# CONN.net
KiCad netlist of a schematic drawn in Altium Designer
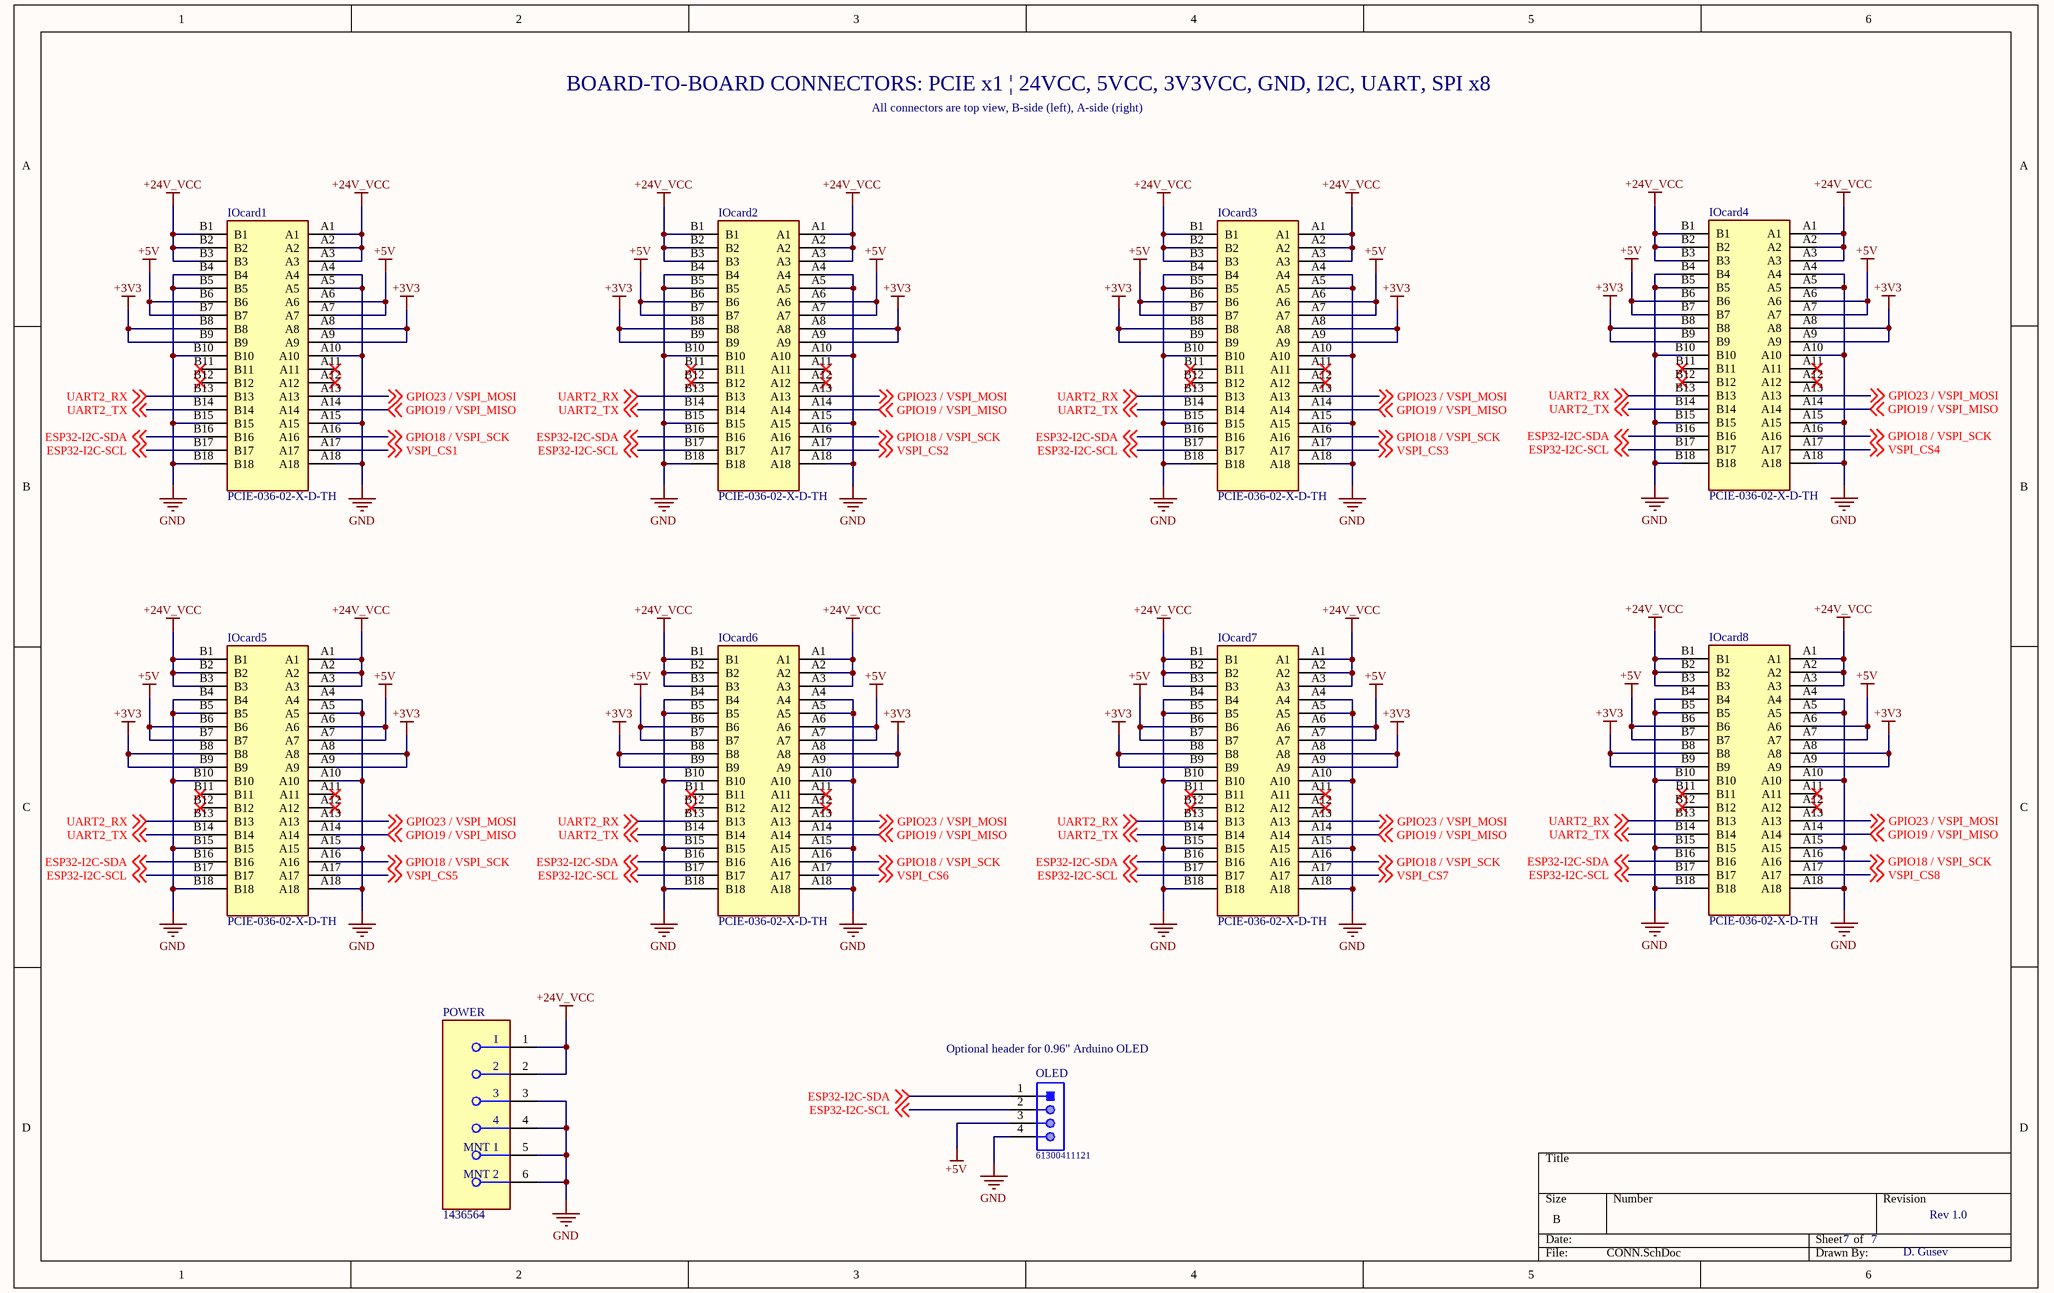
[diagram p0: CONN.SchDoc]

(export (version "E")
  (design (tool "Eeschema 10.0.6"))
  (components
    (comp (ref "IOcard1")
      (value "PCIE-036-02-X-D-TH")
      (footprint "SAMTEC_PCIE-036-02-X-D-TH")
      (description "1.00 mm PCI ExpressÂ® Edge Card Connector")
      (fields (field (name "MF") "Samtec"))
      (libsource (lib "ESP32_INDUSTRIAL_IO_BASEBOARD") (part "PCIE-036-02-X-D-TH"))
    )
    (comp (ref "IOcard2")
      (value "PCIE-036-02-X-D-TH")
      (footprint "SAMTEC_PCIE-036-02-X-D-TH")
      (description "1.00 mm PCI ExpressÂ® Edge Card Connector")
      (fields (field (name "MF") "Samtec"))
      (libsource (lib "ESP32_INDUSTRIAL_IO_BASEBOARD") (part "PCIE-036-02-X-D-TH"))
    )
    (comp (ref "IOcard3")
      (value "PCIE-036-02-X-D-TH")
      (footprint "SAMTEC_PCIE-036-02-X-D-TH")
      (description "1.00 mm PCI ExpressÂ® Edge Card Connector")
      (fields (field (name "MF") "Samtec"))
      (libsource (lib "ESP32_INDUSTRIAL_IO_BASEBOARD") (part "PCIE-036-02-X-D-TH"))
    )
    (comp (ref "IOcard4")
      (value "PCIE-036-02-X-D-TH")
      (footprint "SAMTEC_PCIE-036-02-X-D-TH")
      (description "1.00 mm PCI ExpressÂ® Edge Card Connector")
      (fields (field (name "MF") "Samtec"))
      (libsource (lib "ESP32_INDUSTRIAL_IO_BASEBOARD") (part "PCIE-036-02-X-D-TH"))
    )
    (comp (ref "IOcard5")
      (value "PCIE-036-02-X-D-TH")
      (footprint "SAMTEC_PCIE-036-02-X-D-TH")
      (description "1.00 mm PCI ExpressÂ® Edge Card Connector")
      (fields (field (name "MF") "Samtec"))
      (libsource (lib "ESP32_INDUSTRIAL_IO_BASEBOARD") (part "PCIE-036-02-X-D-TH"))
    )
    (comp (ref "IOcard6")
      (value "PCIE-036-02-X-D-TH")
      (footprint "SAMTEC_PCIE-036-02-X-D-TH")
      (description "1.00 mm PCI ExpressÂ® Edge Card Connector")
      (fields (field (name "MF") "Samtec"))
      (libsource (lib "ESP32_INDUSTRIAL_IO_BASEBOARD") (part "PCIE-036-02-X-D-TH"))
    )
    (comp (ref "IOcard7")
      (value "PCIE-036-02-X-D-TH")
      (footprint "SAMTEC_PCIE-036-02-X-D-TH")
      (description "1.00 mm PCI ExpressÂ® Edge Card Connector")
      (fields (field (name "MF") "Samtec"))
      (libsource (lib "ESP32_INDUSTRIAL_IO_BASEBOARD") (part "PCIE-036-02-X-D-TH"))
    )
    (comp (ref "IOcard8")
      (value "PCIE-036-02-X-D-TH")
      (footprint "SAMTEC_PCIE-036-02-X-D-TH")
      (description "1.00 mm PCI ExpressÂ® Edge Card Connector")
      (fields (field (name "MF") "Samtec"))
      (libsource (lib "ESP32_INDUSTRIAL_IO_BASEBOARD") (part "PCIE-036-02-X-D-TH"))
    )
    (comp (ref "OLED")
      (value "61300411121")
      (footprint "61300411121")
      (description "THT Vertical Pin Header WR-PHD, Pitch 2.54 mm, Single Row, 4 pins")
      (fields (field (name "MANUFACTURER") "Wurth Elektronik") (field (name "PUBLISHER") "WurthElektronik"))
      (libsource (lib "Altium Content Vault") (part "WE-CN-1P-M-R4"))
    )
    (comp (ref "POWER")
      (value "1436564")
      (footprint "FP-1436564-MFG")
      (description "CONN RCPT FMALE 4POS GOLD SOLDER")
      (fields
        (field (name "OCTOPART") "https://octopart.com/1436564-phoenix+contact-12805506")
        (field (name "MANUFACTURER") "Phoenix Contact")
      )
      (libsource (lib "Altium Content Vault") (part "3cf8230c7ca2247c71501eddf00a6f6"))
    )
  )
  (nets
    (net (code "1") (name "+3V3") (class "Default")
      (node (ref "IOcard1") (pin "A8") (pinfunction "A8_A8") (pintype "passive"))
      (node (ref "IOcard1") (pin "A9") (pinfunction "A9_A9") (pintype "passive"))
      (node (ref "IOcard1") (pin "B8") (pinfunction "B8_B8") (pintype "passive"))
      (node (ref "IOcard1") (pin "B9") (pinfunction "B9_B9") (pintype "passive"))
      (node (ref "IOcard2") (pin "A8") (pinfunction "A8_A8") (pintype "passive"))
      (node (ref "IOcard2") (pin "A9") (pinfunction "A9_A9") (pintype "passive"))
      (node (ref "IOcard2") (pin "B8") (pinfunction "B8_B8") (pintype "passive"))
      (node (ref "IOcard2") (pin "B9") (pinfunction "B9_B9") (pintype "passive"))
      (node (ref "IOcard3") (pin "A8") (pinfunction "A8_A8") (pintype "passive"))
      (node (ref "IOcard3") (pin "A9") (pinfunction "A9_A9") (pintype "passive"))
      (node (ref "IOcard3") (pin "B8") (pinfunction "B8_B8") (pintype "passive"))
      (node (ref "IOcard3") (pin "B9") (pinfunction "B9_B9") (pintype "passive"))
      (node (ref "IOcard4") (pin "A8") (pinfunction "A8_A8") (pintype "passive"))
      (node (ref "IOcard4") (pin "A9") (pinfunction "A9_A9") (pintype "passive"))
      (node (ref "IOcard4") (pin "B8") (pinfunction "B8_B8") (pintype "passive"))
      (node (ref "IOcard4") (pin "B9") (pinfunction "B9_B9") (pintype "passive"))
      (node (ref "IOcard5") (pin "A8") (pinfunction "A8_A8") (pintype "passive"))
      (node (ref "IOcard5") (pin "A9") (pinfunction "A9_A9") (pintype "passive"))
      (node (ref "IOcard5") (pin "B8") (pinfunction "B8_B8") (pintype "passive"))
      (node (ref "IOcard5") (pin "B9") (pinfunction "B9_B9") (pintype "passive"))
      (node (ref "IOcard6") (pin "A8") (pinfunction "A8_A8") (pintype "passive"))
      (node (ref "IOcard6") (pin "A9") (pinfunction "A9_A9") (pintype "passive"))
      (node (ref "IOcard6") (pin "B8") (pinfunction "B8_B8") (pintype "passive"))
      (node (ref "IOcard6") (pin "B9") (pinfunction "B9_B9") (pintype "passive"))
      (node (ref "IOcard7") (pin "A8") (pinfunction "A8_A8") (pintype "passive"))
      (node (ref "IOcard7") (pin "A9") (pinfunction "A9_A9") (pintype "passive"))
      (node (ref "IOcard7") (pin "B8") (pinfunction "B8_B8") (pintype "passive"))
      (node (ref "IOcard7") (pin "B9") (pinfunction "B9_B9") (pintype "passive"))
      (node (ref "IOcard8") (pin "A8") (pinfunction "A8_A8") (pintype "passive"))
      (node (ref "IOcard8") (pin "A9") (pinfunction "A9_A9") (pintype "passive"))
      (node (ref "IOcard8") (pin "B8") (pinfunction "B8_B8") (pintype "passive"))
      (node (ref "IOcard8") (pin "B9") (pinfunction "B9_B9") (pintype "passive"))
    )
    (net (code "2") (name "+5V") (class "Default")
      (node (ref "IOcard1") (pin "A6") (pinfunction "A6_A6") (pintype "passive"))
      (node (ref "IOcard1") (pin "A7") (pinfunction "A7_A7") (pintype "passive"))
      (node (ref "IOcard1") (pin "B6") (pinfunction "B6_B6") (pintype "passive"))
      (node (ref "IOcard1") (pin "B7") (pinfunction "B7_B7") (pintype "passive"))
      (node (ref "IOcard2") (pin "A6") (pinfunction "A6_A6") (pintype "passive"))
      (node (ref "IOcard2") (pin "A7") (pinfunction "A7_A7") (pintype "passive"))
      (node (ref "IOcard2") (pin "B6") (pinfunction "B6_B6") (pintype "passive"))
      (node (ref "IOcard2") (pin "B7") (pinfunction "B7_B7") (pintype "passive"))
      (node (ref "IOcard3") (pin "A6") (pinfunction "A6_A6") (pintype "passive"))
      (node (ref "IOcard3") (pin "A7") (pinfunction "A7_A7") (pintype "passive"))
      (node (ref "IOcard3") (pin "B6") (pinfunction "B6_B6") (pintype "passive"))
      (node (ref "IOcard3") (pin "B7") (pinfunction "B7_B7") (pintype "passive"))
      (node (ref "IOcard4") (pin "A6") (pinfunction "A6_A6") (pintype "passive"))
      (node (ref "IOcard4") (pin "A7") (pinfunction "A7_A7") (pintype "passive"))
      (node (ref "IOcard4") (pin "B6") (pinfunction "B6_B6") (pintype "passive"))
      (node (ref "IOcard4") (pin "B7") (pinfunction "B7_B7") (pintype "passive"))
      (node (ref "IOcard5") (pin "A6") (pinfunction "A6_A6") (pintype "passive"))
      (node (ref "IOcard5") (pin "A7") (pinfunction "A7_A7") (pintype "passive"))
      (node (ref "IOcard5") (pin "B6") (pinfunction "B6_B6") (pintype "passive"))
      (node (ref "IOcard5") (pin "B7") (pinfunction "B7_B7") (pintype "passive"))
      (node (ref "IOcard6") (pin "A6") (pinfunction "A6_A6") (pintype "passive"))
      (node (ref "IOcard6") (pin "A7") (pinfunction "A7_A7") (pintype "passive"))
      (node (ref "IOcard6") (pin "B6") (pinfunction "B6_B6") (pintype "passive"))
      (node (ref "IOcard6") (pin "B7") (pinfunction "B7_B7") (pintype "passive"))
      (node (ref "IOcard7") (pin "A6") (pinfunction "A6_A6") (pintype "passive"))
      (node (ref "IOcard7") (pin "A7") (pinfunction "A7_A7") (pintype "passive"))
      (node (ref "IOcard7") (pin "B6") (pinfunction "B6_B6") (pintype "passive"))
      (node (ref "IOcard7") (pin "B7") (pinfunction "B7_B7") (pintype "passive"))
      (node (ref "IOcard8") (pin "A6") (pinfunction "A6_A6") (pintype "passive"))
      (node (ref "IOcard8") (pin "A7") (pinfunction "A7_A7") (pintype "passive"))
      (node (ref "IOcard8") (pin "B6") (pinfunction "B6_B6") (pintype "passive"))
      (node (ref "IOcard8") (pin "B7") (pinfunction "B7_B7") (pintype "passive"))
      (node (ref "OLED") (pin "3") (pinfunction "3_3") (pintype "passive"))
    )
    (net (code "3") (name "+24V_VCC") (class "Default")
      (node (ref "IOcard1") (pin "A1") (pinfunction "A1_A1") (pintype "passive"))
      (node (ref "IOcard1") (pin "A2") (pinfunction "A2_A2") (pintype "passive"))
      (node (ref "IOcard1") (pin "A3") (pinfunction "A3_A3") (pintype "passive"))
      (node (ref "IOcard1") (pin "B1") (pinfunction "B1_B1") (pintype "passive"))
      (node (ref "IOcard1") (pin "B2") (pinfunction "B2_B2") (pintype "passive"))
      (node (ref "IOcard1") (pin "B3") (pinfunction "B3_B3") (pintype "passive"))
      (node (ref "IOcard2") (pin "A1") (pinfunction "A1_A1") (pintype "passive"))
      (node (ref "IOcard2") (pin "A2") (pinfunction "A2_A2") (pintype "passive"))
      (node (ref "IOcard2") (pin "A3") (pinfunction "A3_A3") (pintype "passive"))
      (node (ref "IOcard2") (pin "B1") (pinfunction "B1_B1") (pintype "passive"))
      (node (ref "IOcard2") (pin "B2") (pinfunction "B2_B2") (pintype "passive"))
      (node (ref "IOcard2") (pin "B3") (pinfunction "B3_B3") (pintype "passive"))
      (node (ref "IOcard3") (pin "A1") (pinfunction "A1_A1") (pintype "passive"))
      (node (ref "IOcard3") (pin "A2") (pinfunction "A2_A2") (pintype "passive"))
      (node (ref "IOcard3") (pin "A3") (pinfunction "A3_A3") (pintype "passive"))
      (node (ref "IOcard3") (pin "B1") (pinfunction "B1_B1") (pintype "passive"))
      (node (ref "IOcard3") (pin "B2") (pinfunction "B2_B2") (pintype "passive"))
      (node (ref "IOcard3") (pin "B3") (pinfunction "B3_B3") (pintype "passive"))
      (node (ref "IOcard4") (pin "A1") (pinfunction "A1_A1") (pintype "passive"))
      (node (ref "IOcard4") (pin "A2") (pinfunction "A2_A2") (pintype "passive"))
      (node (ref "IOcard4") (pin "A3") (pinfunction "A3_A3") (pintype "passive"))
      (node (ref "IOcard4") (pin "B1") (pinfunction "B1_B1") (pintype "passive"))
      (node (ref "IOcard4") (pin "B2") (pinfunction "B2_B2") (pintype "passive"))
      (node (ref "IOcard4") (pin "B3") (pinfunction "B3_B3") (pintype "passive"))
      (node (ref "IOcard5") (pin "A1") (pinfunction "A1_A1") (pintype "passive"))
      (node (ref "IOcard5") (pin "A2") (pinfunction "A2_A2") (pintype "passive"))
      (node (ref "IOcard5") (pin "A3") (pinfunction "A3_A3") (pintype "passive"))
      (node (ref "IOcard5") (pin "B1") (pinfunction "B1_B1") (pintype "passive"))
      (node (ref "IOcard5") (pin "B2") (pinfunction "B2_B2") (pintype "passive"))
      (node (ref "IOcard5") (pin "B3") (pinfunction "B3_B3") (pintype "passive"))
      (node (ref "IOcard6") (pin "A1") (pinfunction "A1_A1") (pintype "passive"))
      (node (ref "IOcard6") (pin "A2") (pinfunction "A2_A2") (pintype "passive"))
      (node (ref "IOcard6") (pin "A3") (pinfunction "A3_A3") (pintype "passive"))
      (node (ref "IOcard6") (pin "B1") (pinfunction "B1_B1") (pintype "passive"))
      (node (ref "IOcard6") (pin "B2") (pinfunction "B2_B2") (pintype "passive"))
      (node (ref "IOcard6") (pin "B3") (pinfunction "B3_B3") (pintype "passive"))
      (node (ref "IOcard7") (pin "A1") (pinfunction "A1_A1") (pintype "passive"))
      (node (ref "IOcard7") (pin "A2") (pinfunction "A2_A2") (pintype "passive"))
      (node (ref "IOcard7") (pin "A3") (pinfunction "A3_A3") (pintype "passive"))
      (node (ref "IOcard7") (pin "B1") (pinfunction "B1_B1") (pintype "passive"))
      (node (ref "IOcard7") (pin "B2") (pinfunction "B2_B2") (pintype "passive"))
      (node (ref "IOcard7") (pin "B3") (pinfunction "B3_B3") (pintype "passive"))
      (node (ref "IOcard8") (pin "A1") (pinfunction "A1_A1") (pintype "passive"))
      (node (ref "IOcard8") (pin "A2") (pinfunction "A2_A2") (pintype "passive"))
      (node (ref "IOcard8") (pin "A3") (pinfunction "A3_A3") (pintype "passive"))
      (node (ref "IOcard8") (pin "B1") (pinfunction "B1_B1") (pintype "passive"))
      (node (ref "IOcard8") (pin "B2") (pinfunction "B2_B2") (pintype "passive"))
      (node (ref "IOcard8") (pin "B3") (pinfunction "B3_B3") (pintype "passive"))
      (node (ref "POWER") (pin "1") (pinfunction "1_1") (pintype "passive"))
      (node (ref "POWER") (pin "2") (pinfunction "2_2") (pintype "passive"))
    )
    (net (code "4") (name "ESP32-I2C-SCL") (class "Default")
      (node (ref "IOcard1") (pin "B17") (pinfunction "B17_B17") (pintype "passive"))
      (node (ref "IOcard2") (pin "B17") (pinfunction "B17_B17") (pintype "passive"))
      (node (ref "IOcard3") (pin "B17") (pinfunction "B17_B17") (pintype "passive"))
      (node (ref "IOcard4") (pin "B17") (pinfunction "B17_B17") (pintype "passive"))
      (node (ref "IOcard5") (pin "B17") (pinfunction "B17_B17") (pintype "passive"))
      (node (ref "IOcard6") (pin "B17") (pinfunction "B17_B17") (pintype "passive"))
      (node (ref "IOcard7") (pin "B17") (pinfunction "B17_B17") (pintype "passive"))
      (node (ref "IOcard8") (pin "B17") (pinfunction "B17_B17") (pintype "passive"))
      (node (ref "OLED") (pin "2") (pinfunction "2_2") (pintype "passive"))
    )
    (net (code "5") (name "ESP32-I2C-SDA") (class "Default")
      (node (ref "IOcard1") (pin "B16") (pinfunction "B16_B16") (pintype "passive"))
      (node (ref "IOcard2") (pin "B16") (pinfunction "B16_B16") (pintype "passive"))
      (node (ref "IOcard3") (pin "B16") (pinfunction "B16_B16") (pintype "passive"))
      (node (ref "IOcard4") (pin "B16") (pinfunction "B16_B16") (pintype "passive"))
      (node (ref "IOcard5") (pin "B16") (pinfunction "B16_B16") (pintype "passive"))
      (node (ref "IOcard6") (pin "B16") (pinfunction "B16_B16") (pintype "passive"))
      (node (ref "IOcard7") (pin "B16") (pinfunction "B16_B16") (pintype "passive"))
      (node (ref "IOcard8") (pin "B16") (pinfunction "B16_B16") (pintype "passive"))
      (node (ref "OLED") (pin "1") (pinfunction "1_1") (pintype "passive"))
    )
    (net (code "6") (name "GND") (class "Default")
      (node (ref "IOcard1") (pin "A10") (pinfunction "A10_A10") (pintype "passive"))
      (node (ref "IOcard1") (pin "A15") (pinfunction "A15_A15") (pintype "passive"))
      (node (ref "IOcard1") (pin "A18") (pinfunction "A18_A18") (pintype "passive"))
      (node (ref "IOcard1") (pin "A4") (pinfunction "A4_A4") (pintype "passive"))
      (node (ref "IOcard1") (pin "A5") (pinfunction "A5_A5") (pintype "passive"))
      (node (ref "IOcard1") (pin "B10") (pinfunction "B10_B10") (pintype "passive"))
      (node (ref "IOcard1") (pin "B15") (pinfunction "B15_B15") (pintype "passive"))
      (node (ref "IOcard1") (pin "B18") (pinfunction "B18_B18") (pintype "passive"))
      (node (ref "IOcard1") (pin "B4") (pinfunction "B4_B4") (pintype "passive"))
      (node (ref "IOcard1") (pin "B5") (pinfunction "B5_B5") (pintype "passive"))
      (node (ref "IOcard2") (pin "A10") (pinfunction "A10_A10") (pintype "passive"))
      (node (ref "IOcard2") (pin "A15") (pinfunction "A15_A15") (pintype "passive"))
      (node (ref "IOcard2") (pin "A18") (pinfunction "A18_A18") (pintype "passive"))
      (node (ref "IOcard2") (pin "A4") (pinfunction "A4_A4") (pintype "passive"))
      (node (ref "IOcard2") (pin "A5") (pinfunction "A5_A5") (pintype "passive"))
      (node (ref "IOcard2") (pin "B10") (pinfunction "B10_B10") (pintype "passive"))
      (node (ref "IOcard2") (pin "B15") (pinfunction "B15_B15") (pintype "passive"))
      (node (ref "IOcard2") (pin "B18") (pinfunction "B18_B18") (pintype "passive"))
      (node (ref "IOcard2") (pin "B4") (pinfunction "B4_B4") (pintype "passive"))
      (node (ref "IOcard2") (pin "B5") (pinfunction "B5_B5") (pintype "passive"))
      (node (ref "IOcard3") (pin "A10") (pinfunction "A10_A10") (pintype "passive"))
      (node (ref "IOcard3") (pin "A15") (pinfunction "A15_A15") (pintype "passive"))
      (node (ref "IOcard3") (pin "A18") (pinfunction "A18_A18") (pintype "passive"))
      (node (ref "IOcard3") (pin "A4") (pinfunction "A4_A4") (pintype "passive"))
      (node (ref "IOcard3") (pin "A5") (pinfunction "A5_A5") (pintype "passive"))
      (node (ref "IOcard3") (pin "B10") (pinfunction "B10_B10") (pintype "passive"))
      (node (ref "IOcard3") (pin "B15") (pinfunction "B15_B15") (pintype "passive"))
      (node (ref "IOcard3") (pin "B18") (pinfunction "B18_B18") (pintype "passive"))
      (node (ref "IOcard3") (pin "B4") (pinfunction "B4_B4") (pintype "passive"))
      (node (ref "IOcard3") (pin "B5") (pinfunction "B5_B5") (pintype "passive"))
      (node (ref "IOcard4") (pin "A10") (pinfunction "A10_A10") (pintype "passive"))
      (node (ref "IOcard4") (pin "A15") (pinfunction "A15_A15") (pintype "passive"))
      (node (ref "IOcard4") (pin "A18") (pinfunction "A18_A18") (pintype "passive"))
      (node (ref "IOcard4") (pin "A4") (pinfunction "A4_A4") (pintype "passive"))
      (node (ref "IOcard4") (pin "A5") (pinfunction "A5_A5") (pintype "passive"))
      (node (ref "IOcard4") (pin "B10") (pinfunction "B10_B10") (pintype "passive"))
      (node (ref "IOcard4") (pin "B15") (pinfunction "B15_B15") (pintype "passive"))
      (node (ref "IOcard4") (pin "B18") (pinfunction "B18_B18") (pintype "passive"))
      (node (ref "IOcard4") (pin "B4") (pinfunction "B4_B4") (pintype "passive"))
      (node (ref "IOcard4") (pin "B5") (pinfunction "B5_B5") (pintype "passive"))
      (node (ref "IOcard5") (pin "A10") (pinfunction "A10_A10") (pintype "passive"))
      (node (ref "IOcard5") (pin "A15") (pinfunction "A15_A15") (pintype "passive"))
      (node (ref "IOcard5") (pin "A18") (pinfunction "A18_A18") (pintype "passive"))
      (node (ref "IOcard5") (pin "A4") (pinfunction "A4_A4") (pintype "passive"))
      (node (ref "IOcard5") (pin "A5") (pinfunction "A5_A5") (pintype "passive"))
      (node (ref "IOcard5") (pin "B10") (pinfunction "B10_B10") (pintype "passive"))
      (node (ref "IOcard5") (pin "B15") (pinfunction "B15_B15") (pintype "passive"))
      (node (ref "IOcard5") (pin "B18") (pinfunction "B18_B18") (pintype "passive"))
      (node (ref "IOcard5") (pin "B4") (pinfunction "B4_B4") (pintype "passive"))
      (node (ref "IOcard5") (pin "B5") (pinfunction "B5_B5") (pintype "passive"))
      (node (ref "IOcard6") (pin "A10") (pinfunction "A10_A10") (pintype "passive"))
      (node (ref "IOcard6") (pin "A15") (pinfunction "A15_A15") (pintype "passive"))
      (node (ref "IOcard6") (pin "A18") (pinfunction "A18_A18") (pintype "passive"))
      (node (ref "IOcard6") (pin "A4") (pinfunction "A4_A4") (pintype "passive"))
      (node (ref "IOcard6") (pin "A5") (pinfunction "A5_A5") (pintype "passive"))
      (node (ref "IOcard6") (pin "B10") (pinfunction "B10_B10") (pintype "passive"))
      (node (ref "IOcard6") (pin "B15") (pinfunction "B15_B15") (pintype "passive"))
      (node (ref "IOcard6") (pin "B18") (pinfunction "B18_B18") (pintype "passive"))
      (node (ref "IOcard6") (pin "B4") (pinfunction "B4_B4") (pintype "passive"))
      (node (ref "IOcard6") (pin "B5") (pinfunction "B5_B5") (pintype "passive"))
      (node (ref "IOcard7") (pin "A10") (pinfunction "A10_A10") (pintype "passive"))
      (node (ref "IOcard7") (pin "A15") (pinfunction "A15_A15") (pintype "passive"))
      (node (ref "IOcard7") (pin "A18") (pinfunction "A18_A18") (pintype "passive"))
      (node (ref "IOcard7") (pin "A4") (pinfunction "A4_A4") (pintype "passive"))
      (node (ref "IOcard7") (pin "A5") (pinfunction "A5_A5") (pintype "passive"))
      (node (ref "IOcard7") (pin "B10") (pinfunction "B10_B10") (pintype "passive"))
      (node (ref "IOcard7") (pin "B15") (pinfunction "B15_B15") (pintype "passive"))
      (node (ref "IOcard7") (pin "B18") (pinfunction "B18_B18") (pintype "passive"))
      (node (ref "IOcard7") (pin "B4") (pinfunction "B4_B4") (pintype "passive"))
      (node (ref "IOcard7") (pin "B5") (pinfunction "B5_B5") (pintype "passive"))
      (node (ref "IOcard8") (pin "A10") (pinfunction "A10_A10") (pintype "passive"))
      (node (ref "IOcard8") (pin "A15") (pinfunction "A15_A15") (pintype "passive"))
      (node (ref "IOcard8") (pin "A18") (pinfunction "A18_A18") (pintype "passive"))
      (node (ref "IOcard8") (pin "A4") (pinfunction "A4_A4") (pintype "passive"))
      (node (ref "IOcard8") (pin "A5") (pinfunction "A5_A5") (pintype "passive"))
      (node (ref "IOcard8") (pin "B10") (pinfunction "B10_B10") (pintype "passive"))
      (node (ref "IOcard8") (pin "B15") (pinfunction "B15_B15") (pintype "passive"))
      (node (ref "IOcard8") (pin "B18") (pinfunction "B18_B18") (pintype "passive"))
      (node (ref "IOcard8") (pin "B4") (pinfunction "B4_B4") (pintype "passive"))
      (node (ref "IOcard8") (pin "B5") (pinfunction "B5_B5") (pintype "passive"))
      (node (ref "OLED") (pin "4") (pinfunction "4_4") (pintype "passive"))
      (node (ref "POWER") (pin "3") (pinfunction "3_3") (pintype "passive"))
      (node (ref "POWER") (pin "4") (pinfunction "4_4") (pintype "passive"))
      (node (ref "POWER") (pin "5") (pinfunction "MNT_1_5") (pintype "passive"))
      (node (ref "POWER") (pin "6") (pinfunction "MNT_2_6") (pintype "passive"))
    )
    (net (code "7") (name "GPIO18 {slash} VSPI_SCK") (class "Default")
      (node (ref "IOcard1") (pin "A16") (pinfunction "A16_A16") (pintype "passive"))
      (node (ref "IOcard2") (pin "A16") (pinfunction "A16_A16") (pintype "passive"))
      (node (ref "IOcard3") (pin "A16") (pinfunction "A16_A16") (pintype "passive"))
      (node (ref "IOcard4") (pin "A16") (pinfunction "A16_A16") (pintype "passive"))
      (node (ref "IOcard5") (pin "A16") (pinfunction "A16_A16") (pintype "passive"))
      (node (ref "IOcard6") (pin "A16") (pinfunction "A16_A16") (pintype "passive"))
      (node (ref "IOcard7") (pin "A16") (pinfunction "A16_A16") (pintype "passive"))
      (node (ref "IOcard8") (pin "A16") (pinfunction "A16_A16") (pintype "passive"))
    )
    (net (code "8") (name "GPIO19 {slash} VSPI_MISO") (class "Default")
      (node (ref "IOcard1") (pin "A14") (pinfunction "A14_A14") (pintype "passive"))
      (node (ref "IOcard2") (pin "A14") (pinfunction "A14_A14") (pintype "passive"))
      (node (ref "IOcard3") (pin "A14") (pinfunction "A14_A14") (pintype "passive"))
      (node (ref "IOcard4") (pin "A14") (pinfunction "A14_A14") (pintype "passive"))
      (node (ref "IOcard5") (pin "A14") (pinfunction "A14_A14") (pintype "passive"))
      (node (ref "IOcard6") (pin "A14") (pinfunction "A14_A14") (pintype "passive"))
      (node (ref "IOcard7") (pin "A14") (pinfunction "A14_A14") (pintype "passive"))
      (node (ref "IOcard8") (pin "A14") (pinfunction "A14_A14") (pintype "passive"))
    )
    (net (code "9") (name "GPIO23 {slash} VSPI_MOSI") (class "Default")
      (node (ref "IOcard1") (pin "A13") (pinfunction "A13_A13") (pintype "passive"))
      (node (ref "IOcard2") (pin "A13") (pinfunction "A13_A13") (pintype "passive"))
      (node (ref "IOcard3") (pin "A13") (pinfunction "A13_A13") (pintype "passive"))
      (node (ref "IOcard4") (pin "A13") (pinfunction "A13_A13") (pintype "passive"))
      (node (ref "IOcard5") (pin "A13") (pinfunction "A13_A13") (pintype "passive"))
      (node (ref "IOcard6") (pin "A13") (pinfunction "A13_A13") (pintype "passive"))
      (node (ref "IOcard7") (pin "A13") (pinfunction "A13_A13") (pintype "passive"))
      (node (ref "IOcard8") (pin "A13") (pinfunction "A13_A13") (pintype "passive"))
    )
    (net (code "10") (name "UART2_RX") (class "Default")
      (node (ref "IOcard1") (pin "B13") (pinfunction "B13_B13") (pintype "passive"))
      (node (ref "IOcard2") (pin "B13") (pinfunction "B13_B13") (pintype "passive"))
      (node (ref "IOcard3") (pin "B13") (pinfunction "B13_B13") (pintype "passive"))
      (node (ref "IOcard4") (pin "B13") (pinfunction "B13_B13") (pintype "passive"))
      (node (ref "IOcard5") (pin "B13") (pinfunction "B13_B13") (pintype "passive"))
      (node (ref "IOcard6") (pin "B13") (pinfunction "B13_B13") (pintype "passive"))
      (node (ref "IOcard7") (pin "B13") (pinfunction "B13_B13") (pintype "passive"))
      (node (ref "IOcard8") (pin "B13") (pinfunction "B13_B13") (pintype "passive"))
    )
    (net (code "11") (name "UART2_TX") (class "Default")
      (node (ref "IOcard1") (pin "B14") (pinfunction "B14_B14") (pintype "passive"))
      (node (ref "IOcard2") (pin "B14") (pinfunction "B14_B14") (pintype "passive"))
      (node (ref "IOcard3") (pin "B14") (pinfunction "B14_B14") (pintype "passive"))
      (node (ref "IOcard4") (pin "B14") (pinfunction "B14_B14") (pintype "passive"))
      (node (ref "IOcard5") (pin "B14") (pinfunction "B14_B14") (pintype "passive"))
      (node (ref "IOcard6") (pin "B14") (pinfunction "B14_B14") (pintype "passive"))
      (node (ref "IOcard7") (pin "B14") (pinfunction "B14_B14") (pintype "passive"))
      (node (ref "IOcard8") (pin "B14") (pinfunction "B14_B14") (pintype "passive"))
    )
    (net (code "12") (name "VSPI_CS1") (class "Default")
      (node (ref "IOcard1") (pin "A17") (pinfunction "A17_A17") (pintype "passive"))
    )
    (net (code "13") (name "VSPI_CS2") (class "Default")
      (node (ref "IOcard2") (pin "A17") (pinfunction "A17_A17") (pintype "passive"))
    )
    (net (code "14") (name "VSPI_CS3") (class "Default")
      (node (ref "IOcard3") (pin "A17") (pinfunction "A17_A17") (pintype "passive"))
    )
    (net (code "15") (name "VSPI_CS4") (class "Default")
      (node (ref "IOcard4") (pin "A17") (pinfunction "A17_A17") (pintype "passive"))
    )
    (net (code "16") (name "VSPI_CS5") (class "Default")
      (node (ref "IOcard5") (pin "A17") (pinfunction "A17_A17") (pintype "passive"))
    )
    (net (code "17") (name "VSPI_CS6") (class "Default")
      (node (ref "IOcard6") (pin "A17") (pinfunction "A17_A17") (pintype "passive"))
    )
    (net (code "18") (name "VSPI_CS7") (class "Default")
      (node (ref "IOcard7") (pin "A17") (pinfunction "A17_A17") (pintype "passive"))
    )
    (net (code "19") (name "VSPI_CS8") (class "Default")
      (node (ref "IOcard8") (pin "A17") (pinfunction "A17_A17") (pintype "passive"))
    )
    (net (code "20") (name "unconnected-(IOcard1-PadA11)") (class "Default")
      (node (ref "IOcard1") (pin "A11") (pinfunction "A11_A11") (pintype "passive+no_connect"))
    )
    (net (code "21") (name "unconnected-(IOcard1-PadA12)") (class "Default")
      (node (ref "IOcard1") (pin "A12") (pinfunction "A12_A12") (pintype "passive+no_connect"))
    )
    (net (code "22") (name "unconnected-(IOcard1-PadB11)") (class "Default")
      (node (ref "IOcard1") (pin "B11") (pinfunction "B11_B11") (pintype "passive+no_connect"))
    )
    (net (code "23") (name "unconnected-(IOcard1-PadB12)") (class "Default")
      (node (ref "IOcard1") (pin "B12") (pinfunction "B12_B12") (pintype "passive+no_connect"))
    )
    (net (code "24") (name "unconnected-(IOcard2-PadA11)") (class "Default")
      (node (ref "IOcard2") (pin "A11") (pinfunction "A11_A11") (pintype "passive+no_connect"))
    )
    (net (code "25") (name "unconnected-(IOcard2-PadA12)") (class "Default")
      (node (ref "IOcard2") (pin "A12") (pinfunction "A12_A12") (pintype "passive+no_connect"))
    )
    (net (code "26") (name "unconnected-(IOcard2-PadB11)") (class "Default")
      (node (ref "IOcard2") (pin "B11") (pinfunction "B11_B11") (pintype "passive+no_connect"))
    )
    (net (code "27") (name "unconnected-(IOcard2-PadB12)") (class "Default")
      (node (ref "IOcard2") (pin "B12") (pinfunction "B12_B12") (pintype "passive+no_connect"))
    )
    (net (code "28") (name "unconnected-(IOcard3-PadA11)") (class "Default")
      (node (ref "IOcard3") (pin "A11") (pinfunction "A11_A11") (pintype "passive+no_connect"))
    )
    (net (code "29") (name "unconnected-(IOcard3-PadA12)") (class "Default")
      (node (ref "IOcard3") (pin "A12") (pinfunction "A12_A12") (pintype "passive+no_connect"))
    )
    (net (code "30") (name "unconnected-(IOcard3-PadB11)") (class "Default")
      (node (ref "IOcard3") (pin "B11") (pinfunction "B11_B11") (pintype "passive+no_connect"))
    )
    (net (code "31") (name "unconnected-(IOcard3-PadB12)") (class "Default")
      (node (ref "IOcard3") (pin "B12") (pinfunction "B12_B12") (pintype "passive+no_connect"))
    )
    (net (code "32") (name "unconnected-(IOcard4-PadA11)") (class "Default")
      (node (ref "IOcard4") (pin "A11") (pinfunction "A11_A11") (pintype "passive+no_connect"))
    )
    (net (code "33") (name "unconnected-(IOcard4-PadA12)") (class "Default")
      (node (ref "IOcard4") (pin "A12") (pinfunction "A12_A12") (pintype "passive+no_connect"))
    )
    (net (code "34") (name "unconnected-(IOcard4-PadB11)") (class "Default")
      (node (ref "IOcard4") (pin "B11") (pinfunction "B11_B11") (pintype "passive+no_connect"))
    )
    (net (code "35") (name "unconnected-(IOcard4-PadB12)") (class "Default")
      (node (ref "IOcard4") (pin "B12") (pinfunction "B12_B12") (pintype "passive+no_connect"))
    )
    (net (code "36") (name "unconnected-(IOcard5-PadA11)") (class "Default")
      (node (ref "IOcard5") (pin "A11") (pinfunction "A11_A11") (pintype "passive+no_connect"))
    )
    (net (code "37") (name "unconnected-(IOcard5-PadA12)") (class "Default")
      (node (ref "IOcard5") (pin "A12") (pinfunction "A12_A12") (pintype "passive+no_connect"))
    )
    (net (code "38") (name "unconnected-(IOcard5-PadB11)") (class "Default")
      (node (ref "IOcard5") (pin "B11") (pinfunction "B11_B11") (pintype "passive+no_connect"))
    )
    (net (code "39") (name "unconnected-(IOcard5-PadB12)") (class "Default")
      (node (ref "IOcard5") (pin "B12") (pinfunction "B12_B12") (pintype "passive+no_connect"))
    )
    (net (code "40") (name "unconnected-(IOcard6-PadA11)") (class "Default")
      (node (ref "IOcard6") (pin "A11") (pinfunction "A11_A11") (pintype "passive+no_connect"))
    )
    (net (code "41") (name "unconnected-(IOcard6-PadA12)") (class "Default")
      (node (ref "IOcard6") (pin "A12") (pinfunction "A12_A12") (pintype "passive+no_connect"))
    )
    (net (code "42") (name "unconnected-(IOcard6-PadB11)") (class "Default")
      (node (ref "IOcard6") (pin "B11") (pinfunction "B11_B11") (pintype "passive+no_connect"))
    )
    (net (code "43") (name "unconnected-(IOcard6-PadB12)") (class "Default")
      (node (ref "IOcard6") (pin "B12") (pinfunction "B12_B12") (pintype "passive+no_connect"))
    )
    (net (code "44") (name "unconnected-(IOcard7-PadA11)") (class "Default")
      (node (ref "IOcard7") (pin "A11") (pinfunction "A11_A11") (pintype "passive+no_connect"))
    )
    (net (code "45") (name "unconnected-(IOcard7-PadA12)") (class "Default")
      (node (ref "IOcard7") (pin "A12") (pinfunction "A12_A12") (pintype "passive+no_connect"))
    )
    (net (code "46") (name "unconnected-(IOcard7-PadB11)") (class "Default")
      (node (ref "IOcard7") (pin "B11") (pinfunction "B11_B11") (pintype "passive+no_connect"))
    )
    (net (code "47") (name "unconnected-(IOcard7-PadB12)") (class "Default")
      (node (ref "IOcard7") (pin "B12") (pinfunction "B12_B12") (pintype "passive+no_connect"))
    )
    (net (code "48") (name "unconnected-(IOcard8-PadA11)") (class "Default")
      (node (ref "IOcard8") (pin "A11") (pinfunction "A11_A11") (pintype "passive+no_connect"))
    )
    (net (code "49") (name "unconnected-(IOcard8-PadA12)") (class "Default")
      (node (ref "IOcard8") (pin "A12") (pinfunction "A12_A12") (pintype "passive+no_connect"))
    )
    (net (code "50") (name "unconnected-(IOcard8-PadB11)") (class "Default")
      (node (ref "IOcard8") (pin "B11") (pinfunction "B11_B11") (pintype "passive+no_connect"))
    )
    (net (code "51") (name "unconnected-(IOcard8-PadB12)") (class "Default")
      (node (ref "IOcard8") (pin "B12") (pinfunction "B12_B12") (pintype "passive+no_connect"))
    )
  )
)
